# C2LH_B2B.net
KiCad netlist of a schematic drawn in Altium Designer
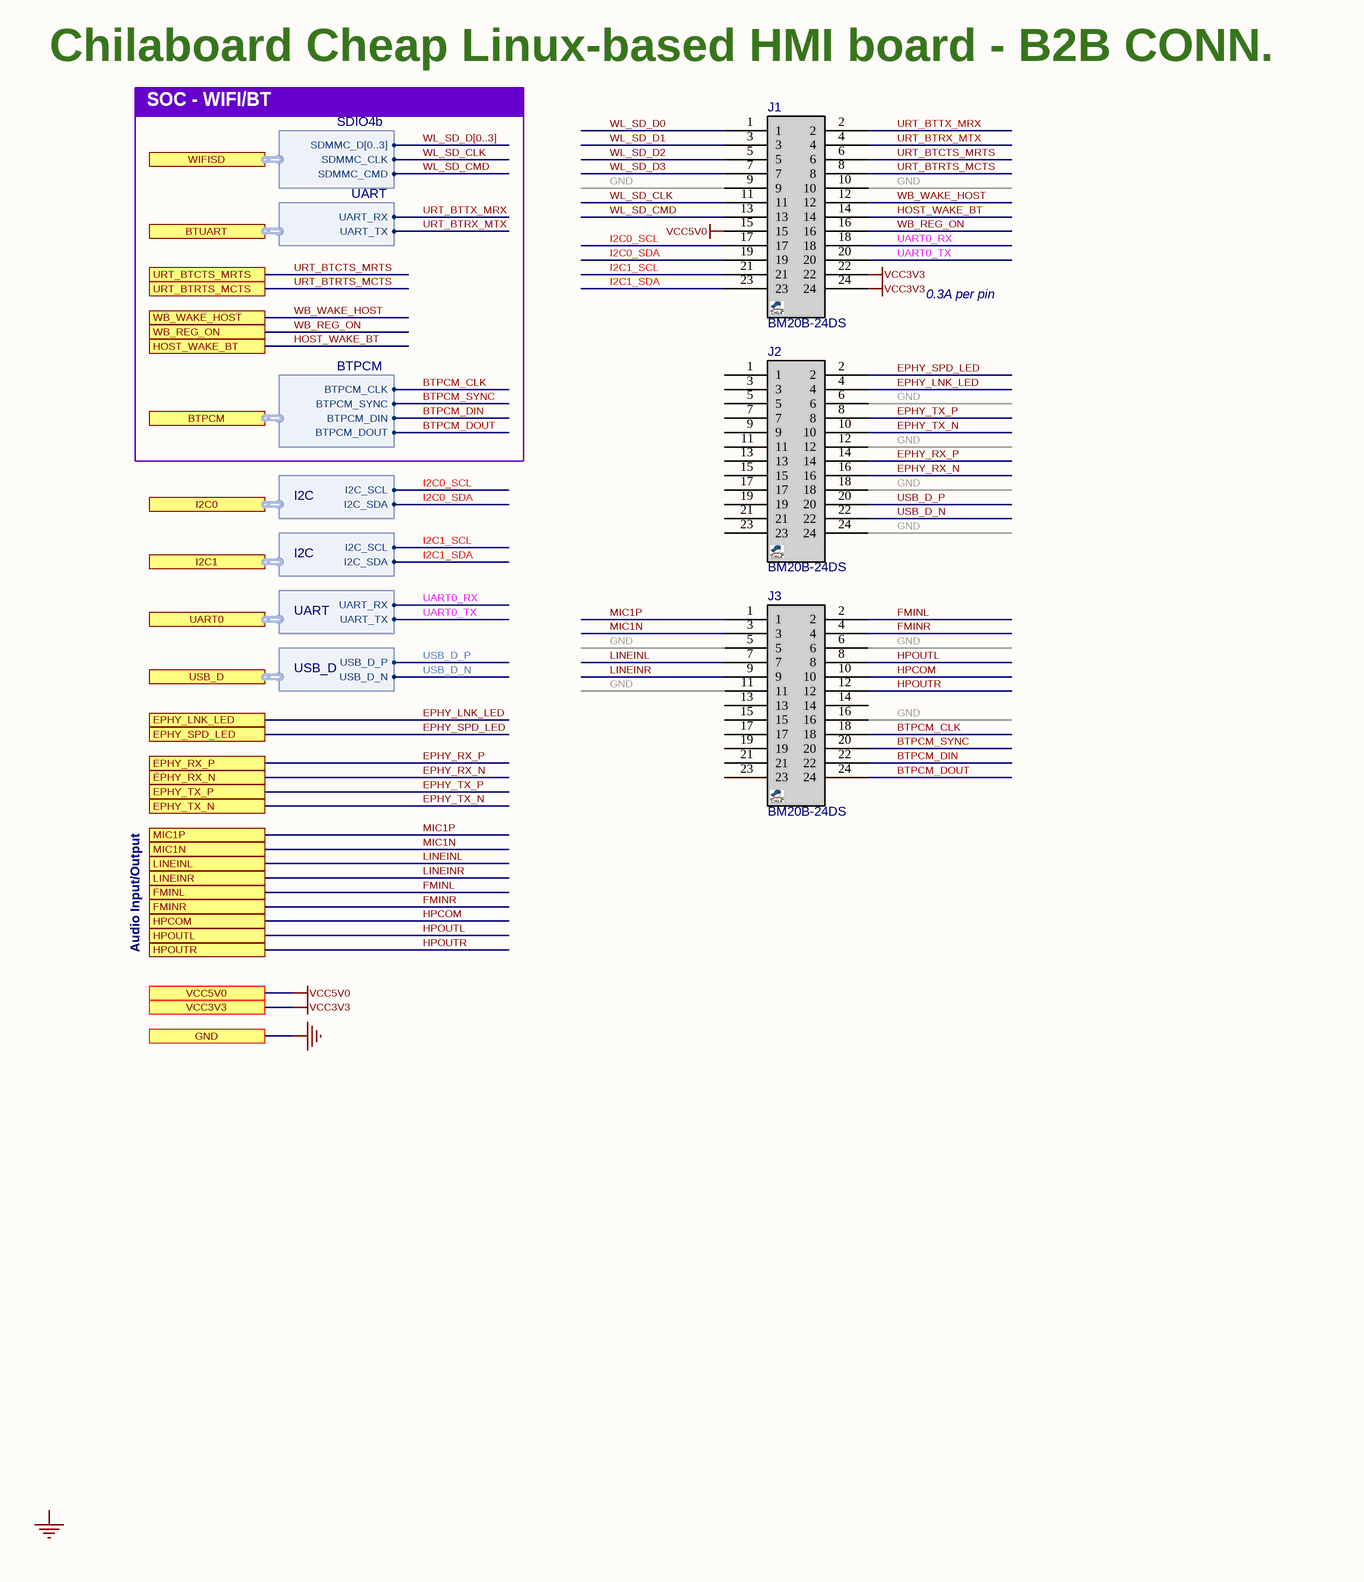
[diagram p0: C2LH_B2B.SchDoc]

(export (version "E")
  (design (tool "Eeschema 10.0.6"))
  (components
    (comp (ref "J1")
      (value "BM20B-24DS")
      (footprint "BM20B_24DS")
      (description "DF23 Series B2B Connectors")
      (fields (field (name "MANF") "HIROSE") (field (name "MANF_P#") "BM20B(0.8)-24DS-0.4V(51)"))
      (libsource (lib "conn_b2b") (part "BM20B-24DS"))
    )
    (comp (ref "J2")
      (value "BM20B-24DS")
      (footprint "BM20B_24DS")
      (description "DF23 Series B2B Connectors")
      (fields (field (name "MANF") "HIROSE") (field (name "MANF_P#") "BM20B(0.8)-24DS-0.4V(51)"))
      (libsource (lib "conn_b2b") (part "BM20B-24DS"))
    )
    (comp (ref "J3")
      (value "BM20B-24DS")
      (footprint "BM20B_24DS")
      (description "DF23 Series B2B Connectors")
      (fields (field (name "MANF") "HIROSE") (field (name "MANF_P#") "BM20B(0.8)-24DS-0.4V(51)"))
      (libsource (lib "conn_b2b") (part "BM20B-24DS"))
    )
  )
  (nets
    (net (code "6") (name "/BTPCM_CLK") (class "Default")
      (node (ref "J3") (pin "18") (pinfunction "18_18") (pintype "passive"))
    )
    (net (code "7") (name "/BTPCM_DIN") (class "Default")
      (node (ref "J3") (pin "22") (pinfunction "22_22") (pintype "passive"))
    )
    (net (code "8") (name "/BTPCM_DOUT") (class "Default")
      (node (ref "J3") (pin "24") (pinfunction "24_24") (pintype "passive"))
    )
    (net (code "9") (name "/BTPCM_SYNC") (class "Default")
      (node (ref "J3") (pin "20") (pinfunction "20_20") (pintype "passive"))
    )
    (net (code "10") (name "/EPHY_LNK_LED") (class "Default")
      (node (ref "J2") (pin "4") (pinfunction "4_4") (pintype "passive"))
    )
    (net (code "11") (name "/EPHY_RX_N") (class "Default")
      (node (ref "J2") (pin "16") (pinfunction "16_16") (pintype "passive"))
    )
    (net (code "12") (name "/EPHY_RX_P") (class "Default")
      (node (ref "J2") (pin "14") (pinfunction "14_14") (pintype "passive"))
    )
    (net (code "13") (name "/EPHY_SPD_LED") (class "Default")
      (node (ref "J2") (pin "2") (pinfunction "2_2") (pintype "passive"))
    )
    (net (code "14") (name "/EPHY_TX_N") (class "Default")
      (node (ref "J2") (pin "10") (pinfunction "10_10") (pintype "passive"))
    )
    (net (code "15") (name "/EPHY_TX_P") (class "Default")
      (node (ref "J2") (pin "8") (pinfunction "8_8") (pintype "passive"))
    )
    (net (code "16") (name "/FMINL") (class "Default")
      (node (ref "J3") (pin "2") (pinfunction "2_2") (pintype "passive"))
    )
    (net (code "17") (name "/FMINR") (class "Default")
      (node (ref "J3") (pin "4") (pinfunction "4_4") (pintype "passive"))
    )
    (net (code "18") (name "/HOST_WAKE_BT") (class "Default")
      (node (ref "J1") (pin "14") (pinfunction "14_14") (pintype "passive"))
    )
    (net (code "19") (name "/HPCOM") (class "Default")
      (node (ref "J3") (pin "10") (pinfunction "10_10") (pintype "passive"))
    )
    (net (code "20") (name "/HPOUTL") (class "Default")
      (node (ref "J3") (pin "8") (pinfunction "8_8") (pintype "passive"))
    )
    (net (code "21") (name "/HPOUTR") (class "Default")
      (node (ref "J3") (pin "12") (pinfunction "12_12") (pintype "passive"))
    )
    (net (code "22") (name "/I2C0_SCL") (class "Default")
      (node (ref "J1") (pin "17") (pinfunction "17_17") (pintype "passive"))
    )
    (net (code "23") (name "/I2C0_SDA") (class "Default")
      (node (ref "J1") (pin "19") (pinfunction "19_19") (pintype "passive"))
    )
    (net (code "24") (name "/I2C1_SCL") (class "Default")
      (node (ref "J1") (pin "21") (pinfunction "21_21") (pintype "passive"))
    )
    (net (code "25") (name "/I2C1_SDA") (class "Default")
      (node (ref "J1") (pin "23") (pinfunction "23_23") (pintype "passive"))
    )
    (net (code "26") (name "/LINEINL") (class "Default")
      (node (ref "J3") (pin "7") (pinfunction "7_7") (pintype "passive"))
    )
    (net (code "27") (name "/LINEINR") (class "Default")
      (node (ref "J3") (pin "9") (pinfunction "9_9") (pintype "passive"))
    )
    (net (code "28") (name "/MIC1N") (class "Default")
      (node (ref "J3") (pin "3") (pinfunction "3_3") (pintype "passive"))
    )
    (net (code "29") (name "/MIC1P") (class "Default")
      (node (ref "J3") (pin "1") (pinfunction "1_1") (pintype "passive"))
    )
    (net (code "30") (name "/UART0_RX") (class "Default")
      (node (ref "J1") (pin "18") (pinfunction "18_18") (pintype "passive"))
    )
    (net (code "31") (name "/UART0_TX") (class "Default")
      (node (ref "J1") (pin "20") (pinfunction "20_20") (pintype "passive"))
    )
    (net (code "32") (name "/URT_BTCTS_MRTS") (class "Default")
      (node (ref "J1") (pin "6") (pinfunction "6_6") (pintype "passive"))
    )
    (net (code "33") (name "/URT_BTRTS_MCTS") (class "Default")
      (node (ref "J1") (pin "8") (pinfunction "8_8") (pintype "passive"))
    )
    (net (code "34") (name "/URT_BTRX_MTX") (class "Default")
      (node (ref "J1") (pin "4") (pinfunction "4_4") (pintype "passive"))
    )
    (net (code "35") (name "/URT_BTTX_MRX") (class "Default")
      (node (ref "J1") (pin "2") (pinfunction "2_2") (pintype "passive"))
    )
    (net (code "36") (name "/USB_D_N") (class "Default")
      (node (ref "J2") (pin "22") (pinfunction "22_22") (pintype "passive"))
    )
    (net (code "37") (name "/USB_D_P") (class "Default")
      (node (ref "J2") (pin "20") (pinfunction "20_20") (pintype "passive"))
    )
    (net (code "38") (name "/WB_REG_ON") (class "Default")
      (node (ref "J1") (pin "16") (pinfunction "16_16") (pintype "passive"))
    )
    (net (code "39") (name "/WB_WAKE_HOST") (class "Default")
      (node (ref "J1") (pin "12") (pinfunction "12_12") (pintype "passive"))
    )
    (net (code "40") (name "/WL_SD_CLK") (class "Default")
      (node (ref "J1") (pin "11") (pinfunction "11_11") (pintype "passive"))
    )
    (net (code "41") (name "/WL_SD_CMD") (class "Default")
      (node (ref "J1") (pin "13") (pinfunction "13_13") (pintype "passive"))
    )
    (net (code "42") (name "/WL_SD_D0") (class "Default")
      (node (ref "J1") (pin "1") (pinfunction "1_1") (pintype "passive"))
    )
    (net (code "43") (name "/WL_SD_D1") (class "Default")
      (node (ref "J1") (pin "3") (pinfunction "3_3") (pintype "passive"))
    )
    (net (code "44") (name "/WL_SD_D2") (class "Default")
      (node (ref "J1") (pin "5") (pinfunction "5_5") (pintype "passive"))
    )
    (net (code "45") (name "/WL_SD_D3") (class "Default")
      (node (ref "J1") (pin "7") (pinfunction "7_7") (pintype "passive"))
    )
    (net (code "52") (name "GND") (class "Default")
      (node (ref "J1") (pin "10") (pinfunction "10_10") (pintype "passive"))
      (node (ref "J1") (pin "9") (pinfunction "9_9") (pintype "passive"))
      (node (ref "J2") (pin "12") (pinfunction "12_12") (pintype "passive"))
      (node (ref "J2") (pin "18") (pinfunction "18_18") (pintype "passive"))
      (node (ref "J2") (pin "24") (pinfunction "24_24") (pintype "passive"))
      (node (ref "J2") (pin "6") (pinfunction "6_6") (pintype "passive"))
      (node (ref "J3") (pin "11") (pinfunction "11_11") (pintype "passive"))
      (node (ref "J3") (pin "16") (pinfunction "16_16") (pintype "passive"))
      (node (ref "J3") (pin "5") (pinfunction "5_5") (pintype "passive"))
      (node (ref "J3") (pin "6") (pinfunction "6_6") (pintype "passive"))
    )
    (net (code "53") (name "VCC3V3") (class "Default")
      (node (ref "J1") (pin "22") (pinfunction "22_22") (pintype "passive"))
      (node (ref "J1") (pin "24") (pinfunction "24_24") (pintype "passive"))
    )
    (net (code "54") (name "VCC5V0") (class "Default")
      (node (ref "J1") (pin "15") (pinfunction "15_15") (pintype "passive"))
    )
    (net (code "55") (name "unconnected-(J2-Pad1)") (class "Default")
      (node (ref "J2") (pin "1") (pinfunction "1_1") (pintype "passive"))
    )
    (net (code "56") (name "unconnected-(J2-Pad3)") (class "Default")
      (node (ref "J2") (pin "3") (pinfunction "3_3") (pintype "passive"))
    )
    (net (code "57") (name "unconnected-(J2-Pad5)") (class "Default")
      (node (ref "J2") (pin "5") (pinfunction "5_5") (pintype "passive"))
    )
    (net (code "58") (name "unconnected-(J2-Pad7)") (class "Default")
      (node (ref "J2") (pin "7") (pinfunction "7_7") (pintype "passive"))
    )
    (net (code "59") (name "unconnected-(J2-Pad9)") (class "Default")
      (node (ref "J2") (pin "9") (pinfunction "9_9") (pintype "passive"))
    )
    (net (code "60") (name "unconnected-(J2-Pad11)") (class "Default")
      (node (ref "J2") (pin "11") (pinfunction "11_11") (pintype "passive"))
    )
    (net (code "61") (name "unconnected-(J2-Pad13)") (class "Default")
      (node (ref "J2") (pin "13") (pinfunction "13_13") (pintype "passive"))
    )
    (net (code "62") (name "unconnected-(J2-Pad15)") (class "Default")
      (node (ref "J2") (pin "15") (pinfunction "15_15") (pintype "passive"))
    )
    (net (code "63") (name "unconnected-(J2-Pad17)") (class "Default")
      (node (ref "J2") (pin "17") (pinfunction "17_17") (pintype "passive"))
    )
    (net (code "64") (name "unconnected-(J2-Pad19)") (class "Default")
      (node (ref "J2") (pin "19") (pinfunction "19_19") (pintype "passive"))
    )
    (net (code "65") (name "unconnected-(J2-Pad21)") (class "Default")
      (node (ref "J2") (pin "21") (pinfunction "21_21") (pintype "passive"))
    )
    (net (code "66") (name "unconnected-(J2-Pad23)") (class "Default")
      (node (ref "J2") (pin "23") (pinfunction "23_23") (pintype "passive"))
    )
    (net (code "67") (name "unconnected-(J3-Pad13)") (class "Default")
      (node (ref "J3") (pin "13") (pinfunction "13_13") (pintype "passive"))
    )
    (net (code "68") (name "unconnected-(J3-Pad14)") (class "Default")
      (node (ref "J3") (pin "14") (pinfunction "14_14") (pintype "passive"))
    )
    (net (code "69") (name "unconnected-(J3-Pad15)") (class "Default")
      (node (ref "J3") (pin "15") (pinfunction "15_15") (pintype "passive"))
    )
    (net (code "70") (name "unconnected-(J3-Pad17)") (class "Default")
      (node (ref "J3") (pin "17") (pinfunction "17_17") (pintype "passive"))
    )
    (net (code "71") (name "unconnected-(J3-Pad19)") (class "Default")
      (node (ref "J3") (pin "19") (pinfunction "19_19") (pintype "passive"))
    )
    (net (code "72") (name "unconnected-(J3-Pad21)") (class "Default")
      (node (ref "J3") (pin "21") (pinfunction "21_21") (pintype "passive"))
    )
    (net (code "73") (name "unconnected-(J3-Pad23)") (class "Default")
      (node (ref "J3") (pin "23") (pinfunction "23_23") (pintype "passive"))
    )
  )
)
